# Sensor_Display.net
KiCad netlist of a schematic drawn in EAGLE
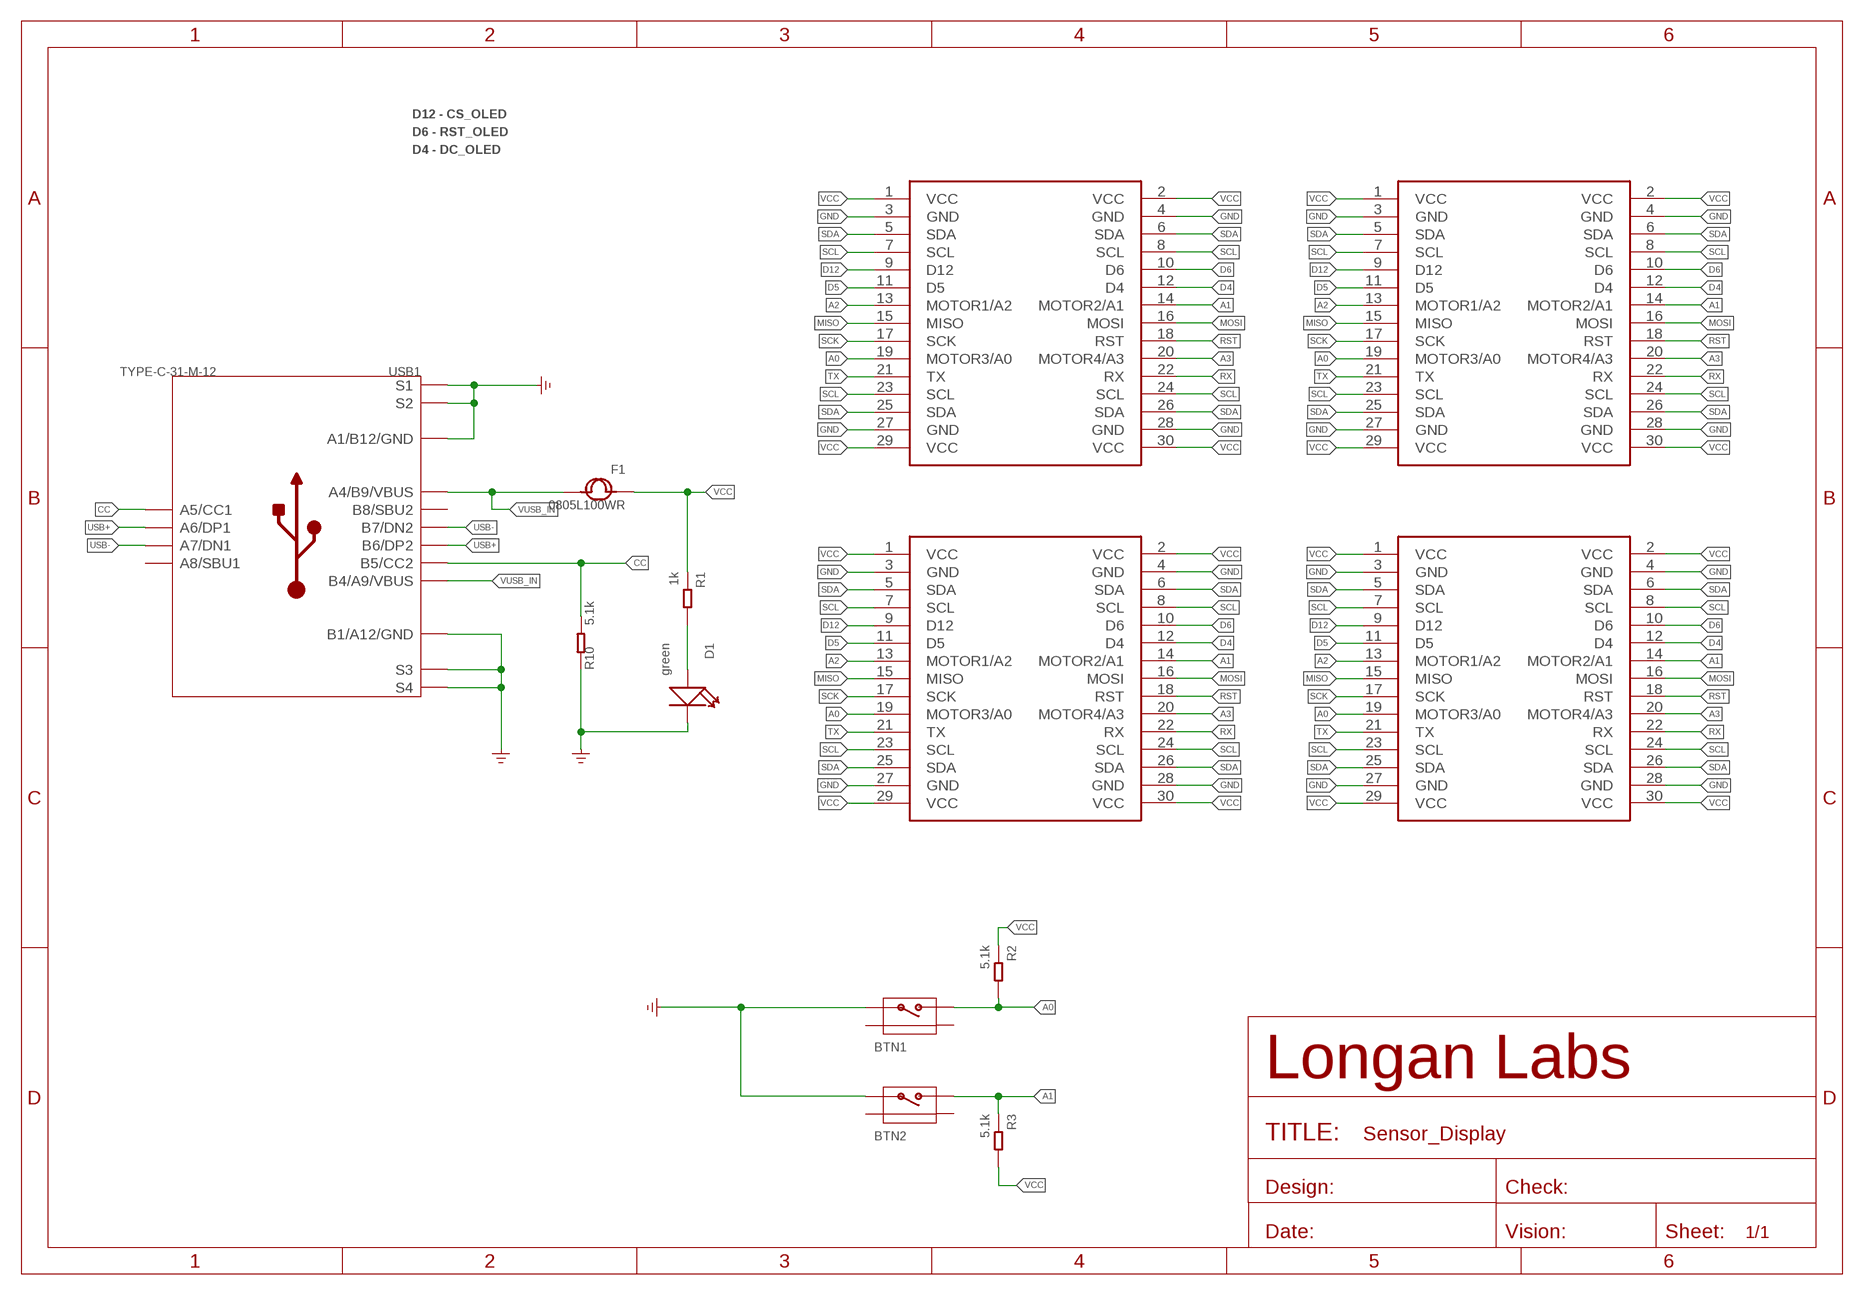
[diagram p0: schematic, sheet 1]

(export (version "E")
  (design (tool "Eeschema 10.0.6"))
  (components
    (comp (ref "BTN1")
      (value "BUTTON-4P-REINFORCE'TS-1188E'")
      (footprint "eagle-import:4P-SMD-7X3.5X3.5H")
      (libsource (lib "eagle-import") (part "BUTTON-4P-REINFORCE'TS-1188E'"))
    )
    (comp (ref "BTN2")
      (value "BUTTON-4P-REINFORCE'TS-1188E'")
      (footprint "eagle-import:4P-SMD-7X3.5X3.5H")
      (libsource (lib "eagle-import") (part "BUTTON-4P-REINFORCE'TS-1188E'"))
    )
    (comp (ref "D1")
      (value "green")
      (footprint "eagle-import:LED-0603")
      (libsource (lib "eagle-import") (part "LED'0603'"))
    )
    (comp (ref "F1")
      (value "0805L100WR")
      (footprint "eagle-import:F0805")
      (libsource (lib "eagle-import") (part "FUSE0805"))
    )
    (comp (ref "MOUDLE1")
      (value "MOUDLE-2X15P-2.54'90D'")
      (footprint "eagle-import:2X15P-2.54-90D")
      (libsource (lib "eagle-import") (part "MOUDLE-2X15P-2.54'90D'"))
    )
    (comp (ref "MOUDLE2")
      (value "MOUDLE-2X15P-2.54'2.54'")
      (footprint "eagle-import:2X15P-2.54")
      (libsource (lib "eagle-import") (part "MOUDLE-2X15P-2.54'2.54'"))
    )
    (comp (ref "MOUDLE3")
      (value "MOUDLE-2X15P-2.54'2.54'")
      (footprint "eagle-import:2X15P-2.54")
      (libsource (lib "eagle-import") (part "MOUDLE-2X15P-2.54'2.54'"))
    )
    (comp (ref "MOUDLE4")
      (value "MOUDLE-2X15P-2.54'2.54'")
      (footprint "eagle-import:2X15P-2.54")
      (libsource (lib "eagle-import") (part "MOUDLE-2X15P-2.54'2.54'"))
    )
    (comp (ref "R1")
      (value "1k")
      (footprint "eagle-import:R0603")
      (libsource (lib "eagle-import") (part "RES-0603"))
    )
    (comp (ref "R2")
      (value "5.1k")
      (footprint "eagle-import:R0603")
      (libsource (lib "eagle-import") (part "RES-0603"))
    )
    (comp (ref "R3")
      (value "5.1k")
      (footprint "eagle-import:R0603")
      (libsource (lib "eagle-import") (part "RES-0603"))
    )
    (comp (ref "R10")
      (value "5.1k")
      (footprint "eagle-import:R0603")
      (libsource (lib "eagle-import") (part "RES-0603"))
    )
    (comp (ref "USB1")
      (value "TYPE-C-31-M-12")
      (footprint "eagle-import:USB2.0-TYPE-C")
      (libsource (lib "eagle-import") (part "USB2.0-TYPE-C"))
    )
  )
  (nets
    (net (code "1") (name "A0") (class "Default")
      (node (ref "BTN1") (pin "2") (pinfunction "2_2") (pintype "bidirectional"))
      (node (ref "MOUDLE1") (pin "19") (pinfunction "MOTOR3/A0_19") (pintype "bidirectional"))
      (node (ref "MOUDLE2") (pin "19") (pinfunction "MOTOR3/A0_19") (pintype "bidirectional"))
      (node (ref "MOUDLE3") (pin "19") (pinfunction "MOTOR3/A0_19") (pintype "bidirectional"))
      (node (ref "MOUDLE4") (pin "19") (pinfunction "MOTOR3/A0_19") (pintype "bidirectional"))
      (node (ref "R2") (pin "2") (pinfunction "2_2") (pintype "passive"))
    )
    (net (code "2") (name "A1") (class "Default")
      (node (ref "BTN2") (pin "2") (pinfunction "2_2") (pintype "bidirectional"))
      (node (ref "MOUDLE1") (pin "14") (pinfunction "MOTOR2/A1_14") (pintype "bidirectional"))
      (node (ref "MOUDLE2") (pin "14") (pinfunction "MOTOR2/A1_14") (pintype "bidirectional"))
      (node (ref "MOUDLE3") (pin "14") (pinfunction "MOTOR2/A1_14") (pintype "bidirectional"))
      (node (ref "MOUDLE4") (pin "14") (pinfunction "MOTOR2/A1_14") (pintype "bidirectional"))
      (node (ref "R3") (pin "1") (pinfunction "1_1") (pintype "passive"))
    )
    (net (code "3") (name "A2") (class "Default")
      (node (ref "MOUDLE1") (pin "13") (pinfunction "MOTOR1/A2_13") (pintype "bidirectional"))
      (node (ref "MOUDLE2") (pin "13") (pinfunction "MOTOR1/A2_13") (pintype "bidirectional"))
      (node (ref "MOUDLE3") (pin "13") (pinfunction "MOTOR1/A2_13") (pintype "bidirectional"))
      (node (ref "MOUDLE4") (pin "13") (pinfunction "MOTOR1/A2_13") (pintype "bidirectional"))
    )
    (net (code "4") (name "A3") (class "Default")
      (node (ref "MOUDLE1") (pin "20") (pinfunction "MOTOR4/A3_20") (pintype "bidirectional"))
      (node (ref "MOUDLE2") (pin "20") (pinfunction "MOTOR4/A3_20") (pintype "bidirectional"))
      (node (ref "MOUDLE3") (pin "20") (pinfunction "MOTOR4/A3_20") (pintype "bidirectional"))
      (node (ref "MOUDLE4") (pin "20") (pinfunction "MOTOR4/A3_20") (pintype "bidirectional"))
    )
    (net (code "5") (name "CC") (class "Default")
      (node (ref "R10") (pin "2") (pinfunction "2_2") (pintype "passive"))
      (node (ref "USB1") (pin "A5") (pinfunction "A5/CC1_A5") (pintype "bidirectional"))
      (node (ref "USB1") (pin "B5") (pinfunction "B5/CC2_B5") (pintype "bidirectional"))
    )
    (net (code "6") (name "D4") (class "Default")
      (node (ref "MOUDLE1") (pin "12") (pinfunction "D4_12") (pintype "bidirectional"))
      (node (ref "MOUDLE2") (pin "12") (pinfunction "D4_12") (pintype "bidirectional"))
      (node (ref "MOUDLE3") (pin "12") (pinfunction "D4_12") (pintype "bidirectional"))
      (node (ref "MOUDLE4") (pin "12") (pinfunction "D4_12") (pintype "bidirectional"))
    )
    (net (code "7") (name "D5") (class "Default")
      (node (ref "MOUDLE1") (pin "11") (pinfunction "D5_11") (pintype "bidirectional"))
      (node (ref "MOUDLE2") (pin "11") (pinfunction "D5_11") (pintype "bidirectional"))
      (node (ref "MOUDLE3") (pin "11") (pinfunction "D5_11") (pintype "bidirectional"))
      (node (ref "MOUDLE4") (pin "11") (pinfunction "D5_11") (pintype "bidirectional"))
    )
    (net (code "8") (name "D6") (class "Default")
      (node (ref "MOUDLE1") (pin "10") (pinfunction "D6_10") (pintype "bidirectional"))
      (node (ref "MOUDLE2") (pin "10") (pinfunction "D6_10") (pintype "bidirectional"))
      (node (ref "MOUDLE3") (pin "10") (pinfunction "D6_10") (pintype "bidirectional"))
      (node (ref "MOUDLE4") (pin "10") (pinfunction "D6_10") (pintype "bidirectional"))
    )
    (net (code "9") (name "D12") (class "Default")
      (node (ref "MOUDLE1") (pin "9") (pinfunction "D12_9") (pintype "bidirectional"))
      (node (ref "MOUDLE2") (pin "9") (pinfunction "D12_9") (pintype "bidirectional"))
      (node (ref "MOUDLE3") (pin "9") (pinfunction "D12_9") (pintype "bidirectional"))
      (node (ref "MOUDLE4") (pin "9") (pinfunction "D12_9") (pintype "bidirectional"))
    )
    (net (code "10") (name "GND") (class "Default")
      (node (ref "BTN1") (pin "1") (pinfunction "1_1") (pintype "bidirectional"))
      (node (ref "BTN2") (pin "1") (pinfunction "1_1") (pintype "bidirectional"))
      (node (ref "D1") (pin "-") (pinfunction "-_-") (pintype "passive"))
      (node (ref "MOUDLE1") (pin "27") (pinfunction "GND_27") (pintype "bidirectional"))
      (node (ref "MOUDLE1") (pin "28") (pinfunction "GND_28") (pintype "bidirectional"))
      (node (ref "MOUDLE1") (pin "3") (pinfunction "GND_3") (pintype "bidirectional"))
      (node (ref "MOUDLE1") (pin "4") (pinfunction "GND_4") (pintype "bidirectional"))
      (node (ref "MOUDLE2") (pin "27") (pinfunction "GND_27") (pintype "bidirectional"))
      (node (ref "MOUDLE2") (pin "28") (pinfunction "GND_28") (pintype "bidirectional"))
      (node (ref "MOUDLE2") (pin "3") (pinfunction "GND_3") (pintype "bidirectional"))
      (node (ref "MOUDLE2") (pin "4") (pinfunction "GND_4") (pintype "bidirectional"))
      (node (ref "MOUDLE3") (pin "27") (pinfunction "GND_27") (pintype "bidirectional"))
      (node (ref "MOUDLE3") (pin "28") (pinfunction "GND_28") (pintype "bidirectional"))
      (node (ref "MOUDLE3") (pin "3") (pinfunction "GND_3") (pintype "bidirectional"))
      (node (ref "MOUDLE3") (pin "4") (pinfunction "GND_4") (pintype "bidirectional"))
      (node (ref "MOUDLE4") (pin "27") (pinfunction "GND_27") (pintype "bidirectional"))
      (node (ref "MOUDLE4") (pin "28") (pinfunction "GND_28") (pintype "bidirectional"))
      (node (ref "MOUDLE4") (pin "3") (pinfunction "GND_3") (pintype "bidirectional"))
      (node (ref "MOUDLE4") (pin "4") (pinfunction "GND_4") (pintype "bidirectional"))
      (node (ref "R10") (pin "1") (pinfunction "1_1") (pintype "passive"))
      (node (ref "USB1") (pin "A1_B12") (pinfunction "A1/B12/GND_A1_B12") (pintype "bidirectional"))
      (node (ref "USB1") (pin "B1_A12") (pinfunction "B1/A12/GND_B1_A12") (pintype "bidirectional"))
      (node (ref "USB1") (pin "S1") (pinfunction "S1_S1") (pintype "bidirectional"))
      (node (ref "USB1") (pin "S2") (pinfunction "S2_S2") (pintype "bidirectional"))
      (node (ref "USB1") (pin "S3") (pinfunction "S3_S3") (pintype "bidirectional"))
      (node (ref "USB1") (pin "S4") (pinfunction "S4_S4") (pintype "bidirectional"))
      (node (ref "USB1") (pin "S5") (pinfunction "S1_S5") (pintype "bidirectional"))
      (node (ref "USB1") (pin "S6") (pinfunction "S2_S6") (pintype "bidirectional"))
    )
    (net (code "11") (name "MISO") (class "Default")
      (node (ref "MOUDLE1") (pin "15") (pinfunction "MISO_15") (pintype "bidirectional"))
      (node (ref "MOUDLE2") (pin "15") (pinfunction "MISO_15") (pintype "bidirectional"))
      (node (ref "MOUDLE3") (pin "15") (pinfunction "MISO_15") (pintype "bidirectional"))
      (node (ref "MOUDLE4") (pin "15") (pinfunction "MISO_15") (pintype "bidirectional"))
    )
    (net (code "12") (name "MOSI") (class "Default")
      (node (ref "MOUDLE1") (pin "16") (pinfunction "MOSI_16") (pintype "bidirectional"))
      (node (ref "MOUDLE2") (pin "16") (pinfunction "MOSI_16") (pintype "bidirectional"))
      (node (ref "MOUDLE3") (pin "16") (pinfunction "MOSI_16") (pintype "bidirectional"))
      (node (ref "MOUDLE4") (pin "16") (pinfunction "MOSI_16") (pintype "bidirectional"))
    )
    (net (code "13") (name "Net-(D1-Pad+)") (class "Default")
      (node (ref "D1") (pin "+") (pinfunction "+_+") (pintype "passive"))
      (node (ref "R1") (pin "2") (pinfunction "2_2") (pintype "passive"))
    )
    (net (code "14") (name "RST") (class "Default")
      (node (ref "MOUDLE1") (pin "18") (pinfunction "RST_18") (pintype "bidirectional"))
      (node (ref "MOUDLE2") (pin "18") (pinfunction "RST_18") (pintype "bidirectional"))
      (node (ref "MOUDLE3") (pin "18") (pinfunction "RST_18") (pintype "bidirectional"))
      (node (ref "MOUDLE4") (pin "18") (pinfunction "RST_18") (pintype "bidirectional"))
    )
    (net (code "15") (name "RX") (class "Default")
      (node (ref "MOUDLE1") (pin "22") (pinfunction "RX_22") (pintype "bidirectional"))
      (node (ref "MOUDLE2") (pin "22") (pinfunction "RX_22") (pintype "bidirectional"))
      (node (ref "MOUDLE3") (pin "22") (pinfunction "RX_22") (pintype "bidirectional"))
      (node (ref "MOUDLE4") (pin "22") (pinfunction "RX_22") (pintype "bidirectional"))
    )
    (net (code "16") (name "SCK") (class "Default")
      (node (ref "MOUDLE1") (pin "17") (pinfunction "SCK_17") (pintype "bidirectional"))
      (node (ref "MOUDLE2") (pin "17") (pinfunction "SCK_17") (pintype "bidirectional"))
      (node (ref "MOUDLE3") (pin "17") (pinfunction "SCK_17") (pintype "bidirectional"))
      (node (ref "MOUDLE4") (pin "17") (pinfunction "SCK_17") (pintype "bidirectional"))
    )
    (net (code "17") (name "SCL") (class "Default")
      (node (ref "MOUDLE1") (pin "23") (pinfunction "SCL_23") (pintype "bidirectional"))
      (node (ref "MOUDLE1") (pin "24") (pinfunction "SCL_24") (pintype "bidirectional"))
      (node (ref "MOUDLE1") (pin "7") (pinfunction "SCL_7") (pintype "bidirectional"))
      (node (ref "MOUDLE1") (pin "8") (pinfunction "SCL_8") (pintype "bidirectional"))
      (node (ref "MOUDLE2") (pin "23") (pinfunction "SCL_23") (pintype "bidirectional"))
      (node (ref "MOUDLE2") (pin "24") (pinfunction "SCL_24") (pintype "bidirectional"))
      (node (ref "MOUDLE2") (pin "7") (pinfunction "SCL_7") (pintype "bidirectional"))
      (node (ref "MOUDLE2") (pin "8") (pinfunction "SCL_8") (pintype "bidirectional"))
      (node (ref "MOUDLE3") (pin "23") (pinfunction "SCL_23") (pintype "bidirectional"))
      (node (ref "MOUDLE3") (pin "24") (pinfunction "SCL_24") (pintype "bidirectional"))
      (node (ref "MOUDLE3") (pin "7") (pinfunction "SCL_7") (pintype "bidirectional"))
      (node (ref "MOUDLE3") (pin "8") (pinfunction "SCL_8") (pintype "bidirectional"))
      (node (ref "MOUDLE4") (pin "23") (pinfunction "SCL_23") (pintype "bidirectional"))
      (node (ref "MOUDLE4") (pin "24") (pinfunction "SCL_24") (pintype "bidirectional"))
      (node (ref "MOUDLE4") (pin "7") (pinfunction "SCL_7") (pintype "bidirectional"))
      (node (ref "MOUDLE4") (pin "8") (pinfunction "SCL_8") (pintype "bidirectional"))
    )
    (net (code "18") (name "SDA") (class "Default")
      (node (ref "MOUDLE1") (pin "25") (pinfunction "SDA_25") (pintype "bidirectional"))
      (node (ref "MOUDLE1") (pin "26") (pinfunction "SDA_26") (pintype "bidirectional"))
      (node (ref "MOUDLE1") (pin "5") (pinfunction "SDA_5") (pintype "bidirectional"))
      (node (ref "MOUDLE1") (pin "6") (pinfunction "SDA_6") (pintype "bidirectional"))
      (node (ref "MOUDLE2") (pin "25") (pinfunction "SDA_25") (pintype "bidirectional"))
      (node (ref "MOUDLE2") (pin "26") (pinfunction "SDA_26") (pintype "bidirectional"))
      (node (ref "MOUDLE2") (pin "5") (pinfunction "SDA_5") (pintype "bidirectional"))
      (node (ref "MOUDLE2") (pin "6") (pinfunction "SDA_6") (pintype "bidirectional"))
      (node (ref "MOUDLE3") (pin "25") (pinfunction "SDA_25") (pintype "bidirectional"))
      (node (ref "MOUDLE3") (pin "26") (pinfunction "SDA_26") (pintype "bidirectional"))
      (node (ref "MOUDLE3") (pin "5") (pinfunction "SDA_5") (pintype "bidirectional"))
      (node (ref "MOUDLE3") (pin "6") (pinfunction "SDA_6") (pintype "bidirectional"))
      (node (ref "MOUDLE4") (pin "25") (pinfunction "SDA_25") (pintype "bidirectional"))
      (node (ref "MOUDLE4") (pin "26") (pinfunction "SDA_26") (pintype "bidirectional"))
      (node (ref "MOUDLE4") (pin "5") (pinfunction "SDA_5") (pintype "bidirectional"))
      (node (ref "MOUDLE4") (pin "6") (pinfunction "SDA_6") (pintype "bidirectional"))
    )
    (net (code "19") (name "TX") (class "Default")
      (node (ref "MOUDLE1") (pin "21") (pinfunction "TX_21") (pintype "bidirectional"))
      (node (ref "MOUDLE2") (pin "21") (pinfunction "TX_21") (pintype "bidirectional"))
      (node (ref "MOUDLE3") (pin "21") (pinfunction "TX_21") (pintype "bidirectional"))
      (node (ref "MOUDLE4") (pin "21") (pinfunction "TX_21") (pintype "bidirectional"))
    )
    (net (code "20") (name "USB+") (class "Default")
      (node (ref "USB1") (pin "A6") (pinfunction "A6/DP1_A6") (pintype "bidirectional"))
      (node (ref "USB1") (pin "B6") (pinfunction "B6/DP2_B6") (pintype "bidirectional"))
    )
    (net (code "21") (name "USB-") (class "Default")
      (node (ref "USB1") (pin "A7") (pinfunction "A7/DN1_A7") (pintype "bidirectional"))
      (node (ref "USB1") (pin "B7") (pinfunction "B7/DN2_B7") (pintype "bidirectional"))
    )
    (net (code "22") (name "VCC") (class "Default")
      (node (ref "F1") (pin "1") (pinfunction "1_1") (pintype "bidirectional"))
      (node (ref "MOUDLE1") (pin "1") (pinfunction "VCC_1") (pintype "bidirectional"))
      (node (ref "MOUDLE1") (pin "2") (pinfunction "VCC_2") (pintype "bidirectional"))
      (node (ref "MOUDLE1") (pin "29") (pinfunction "VCC_29") (pintype "bidirectional"))
      (node (ref "MOUDLE1") (pin "30") (pinfunction "VCC_30") (pintype "bidirectional"))
      (node (ref "MOUDLE2") (pin "1") (pinfunction "VCC_1") (pintype "bidirectional"))
      (node (ref "MOUDLE2") (pin "2") (pinfunction "VCC_2") (pintype "bidirectional"))
      (node (ref "MOUDLE2") (pin "29") (pinfunction "VCC_29") (pintype "bidirectional"))
      (node (ref "MOUDLE2") (pin "30") (pinfunction "VCC_30") (pintype "bidirectional"))
      (node (ref "MOUDLE3") (pin "1") (pinfunction "VCC_1") (pintype "bidirectional"))
      (node (ref "MOUDLE3") (pin "2") (pinfunction "VCC_2") (pintype "bidirectional"))
      (node (ref "MOUDLE3") (pin "29") (pinfunction "VCC_29") (pintype "bidirectional"))
      (node (ref "MOUDLE3") (pin "30") (pinfunction "VCC_30") (pintype "bidirectional"))
      (node (ref "MOUDLE4") (pin "1") (pinfunction "VCC_1") (pintype "bidirectional"))
      (node (ref "MOUDLE4") (pin "2") (pinfunction "VCC_2") (pintype "bidirectional"))
      (node (ref "MOUDLE4") (pin "29") (pinfunction "VCC_29") (pintype "bidirectional"))
      (node (ref "MOUDLE4") (pin "30") (pinfunction "VCC_30") (pintype "bidirectional"))
      (node (ref "R1") (pin "1") (pinfunction "1_1") (pintype "passive"))
      (node (ref "R2") (pin "1") (pinfunction "1_1") (pintype "passive"))
      (node (ref "R3") (pin "2") (pinfunction "2_2") (pintype "passive"))
    )
    (net (code "23") (name "VUSB_IN") (class "Default")
      (node (ref "F1") (pin "2") (pinfunction "2_2") (pintype "bidirectional"))
      (node (ref "USB1") (pin "A4_B9") (pinfunction "A4/B9/VBUS_A4_B9") (pintype "bidirectional"))
      (node (ref "USB1") (pin "B4_A9") (pinfunction "B4/A9/VBUS_B4_A9") (pintype "bidirectional"))
    )
    (net (code "24") (name "unconnected-(BTN1-PadS1)") (class "Default")
      (node (ref "BTN1") (pin "S1") (pinfunction "S1_S1") (pintype "bidirectional"))
    )
    (net (code "25") (name "unconnected-(BTN1-PadS2)") (class "Default")
      (node (ref "BTN1") (pin "S2") (pinfunction "S2_S2") (pintype "bidirectional"))
    )
    (net (code "26") (name "unconnected-(BTN2-PadS1)") (class "Default")
      (node (ref "BTN2") (pin "S1") (pinfunction "S1_S1") (pintype "bidirectional"))
    )
    (net (code "27") (name "unconnected-(BTN2-PadS2)") (class "Default")
      (node (ref "BTN2") (pin "S2") (pinfunction "S2_S2") (pintype "bidirectional"))
    )
    (net (code "28") (name "unconnected-(USB1-A8{slash}SBU1-PadA8)") (class "Default")
      (node (ref "USB1") (pin "A8") (pinfunction "A8/SBU1_A8") (pintype "bidirectional"))
    )
    (net (code "29") (name "unconnected-(USB1-B8{slash}SBU2-PadB8)") (class "Default")
      (node (ref "USB1") (pin "B8") (pinfunction "B8/SBU2_B8") (pintype "bidirectional"))
    )
  )
)
